# Board_Schematic.net
KiCad netlist of a schematic drawn in Altium Designer
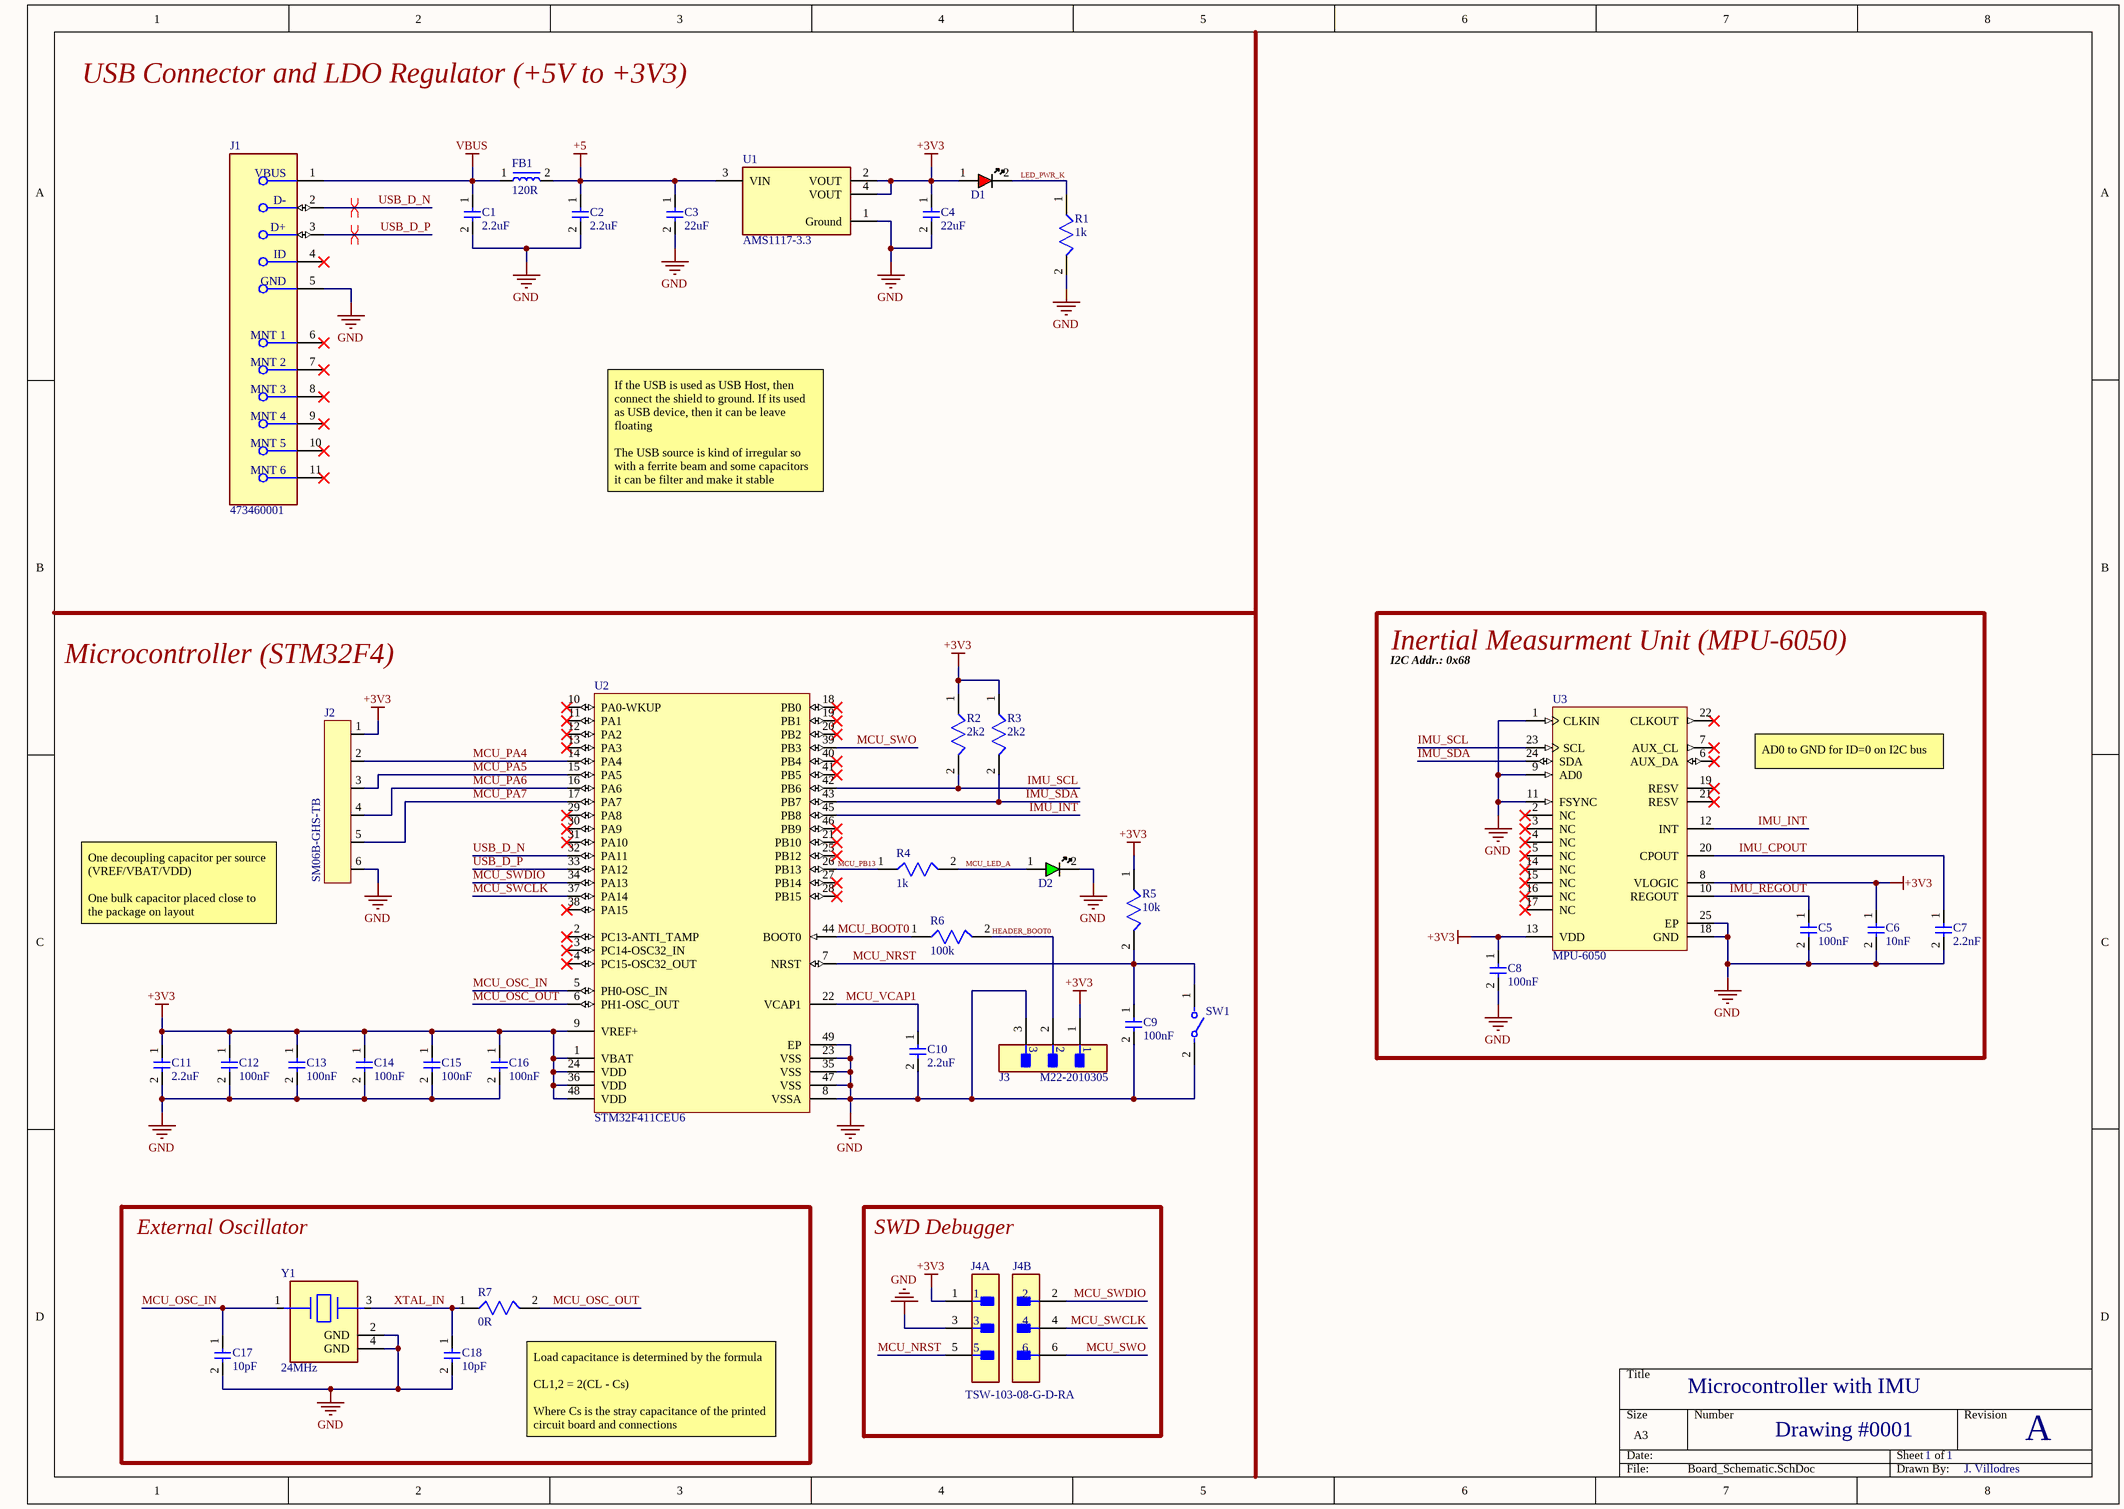
[diagram p0: Board_Schematic.SchDoc]

(export (version "E")
  (design (tool "Eeschema 10.0.6"))
  (components
    (comp (ref "C1")
      (value "2.2uF")
      (footprint "CAPC1608X90N")
      (description "Capacitor SMD 0603 16V")
      (libsource (lib "Schematic-Lib-JVillodres") (part "CAP_0603_16V"))
    )
    (comp (ref "C2")
      (value "2.2uF")
      (footprint "CAPC1608X90N")
      (description "Capacitor SMD 0603 16V")
      (libsource (lib "Schematic-Lib-JVillodres") (part "CAP_0603_16V"))
    )
    (comp (ref "C3")
      (value "22uF")
      (footprint "CAPC2012X95L")
      (description "Capacitor SMD 0805 16V")
      (libsource (lib "Schematic-Lib-JVillodres") (part "CAP_0805_16V"))
    )
    (comp (ref "C4")
      (value "22uF")
      (footprint "CAPC2012X95L")
      (description "Capacitor SMD 0805 16V")
      (libsource (lib "Schematic-Lib-JVillodres") (part "CAP_0805_16V"))
    )
    (comp (ref "C5")
      (value "100nF")
      (footprint "CAPC1005X55N")
      (description "Capacitor SMD 0402 16V")
      (libsource (lib "Schematic-Lib-JVillodres") (part "CAP_0402_16V"))
    )
    (comp (ref "C6")
      (value "10nF")
      (footprint "CAPC1005X55N")
      (description "Capacitor SMD 0402 16V")
      (libsource (lib "Schematic-Lib-JVillodres") (part "CAP_0402_16V"))
    )
    (comp (ref "C7")
      (value "2.2nF")
      (footprint "CAPC1005X55N")
      (description "Capacitor SMD 0402 16V")
      (libsource (lib "Schematic-Lib-JVillodres") (part "CAP_0402_16V"))
    )
    (comp (ref "C8")
      (value "100nF")
      (footprint "CAPC1005X55N")
      (description "Capacitor SMD 0402 16V")
      (libsource (lib "Schematic-Lib-JVillodres") (part "CAP_0402_16V"))
    )
    (comp (ref "C9")
      (value "100nF")
      (footprint "CAPC1005X55N")
      (description "Capacitor SMD 0402 16V")
      (libsource (lib "Schematic-Lib-JVillodres") (part "CAP_0402_16V"))
    )
    (comp (ref "C10")
      (value "2.2uF")
      (footprint "CAPC1608X90N")
      (description "Capacitor SMD 0603 16V")
      (libsource (lib "Schematic-Lib-JVillodres") (part "CAP_0603_16V"))
    )
    (comp (ref "C11")
      (value "2.2uF")
      (footprint "CAPC1608X90N")
      (description "Capacitor SMD 0603 16V")
      (libsource (lib "Schematic-Lib-JVillodres") (part "CAP_0603_16V"))
    )
    (comp (ref "C12")
      (value "100nF")
      (footprint "CAPC1005X55N")
      (description "Capacitor SMD 0402 16V")
      (libsource (lib "Schematic-Lib-JVillodres") (part "CAP_0402_16V"))
    )
    (comp (ref "C13")
      (value "100nF")
      (footprint "CAPC1005X55N")
      (description "Capacitor SMD 0402 16V")
      (libsource (lib "Schematic-Lib-JVillodres") (part "CAP_0402_16V"))
    )
    (comp (ref "C14")
      (value "100nF")
      (footprint "CAPC1005X55N")
      (description "Capacitor SMD 0402 16V")
      (libsource (lib "Schematic-Lib-JVillodres") (part "CAP_0402_16V"))
    )
    (comp (ref "C15")
      (value "100nF")
      (footprint "CAPC1005X55N")
      (description "Capacitor SMD 0402 16V")
      (libsource (lib "Schematic-Lib-JVillodres") (part "CAP_0402_16V"))
    )
    (comp (ref "C16")
      (value "100nF")
      (footprint "CAPC1005X55N")
      (description "Capacitor SMD 0402 16V")
      (libsource (lib "Schematic-Lib-JVillodres") (part "CAP_0402_16V"))
    )
    (comp (ref "C17")
      (value "10pF")
      (footprint "CAPC1005X55N")
      (description "Capacitor SMD 0402 16V")
      (libsource (lib "Schematic-Lib-JVillodres") (part "CAP_0402_16V"))
    )
    (comp (ref "C18")
      (value "10pF")
      (footprint "CAPC1005X55N")
      (description "Capacitor SMD 0402 16V")
      (libsource (lib "Schematic-Lib-JVillodres") (part "CAP_0402_16V"))
    )
    (comp (ref "D1")
      (value "LED_0402_RED")
      (footprint "LEDC0402")
      (description "LED RED SMD 0402")
      (libsource (lib "Schematic-Lib-JVillodres") (part "LED_0402_RED"))
    )
    (comp (ref "D2")
      (value "LED_0402_GREEN")
      (footprint "LEDC0402")
      (description "LED GREEN SMD 0402")
      (libsource (lib "Schematic-Lib-JVillodres") (part "LED_0402_GREEN"))
    )
    (comp (ref "FB1")
      (value "120R")
      (footprint "FBC1608X95L")
      (description "Ferrite Bead SMD 0603")
      (libsource (lib "Schematic-Lib-JVillodres") (part "FB_0603"))
    )
    (comp (ref "J1")
      (value "473460001")
      (footprint "FP-473460001-MFG")
      (description "CONN RCPT USB2.0 MICRO B SMD R/A")
      (fields
        (field (name "OCTOPART") "https://octopart.com/47346-0001-molex-7164928")
        (field (name "MANUFACTURER") "Molex")
      )
      (libsource (lib "Altium Content Vault") (part "53ae1f1d9b557310b43ca686e5bb76a"))
    )
    (comp (ref "J2")
      (value "SM06B-GHS-TB")
      (footprint "SM06B-GHS-TB")
      (description "Header Connector 6-Pin")
      (libsource (lib "Schematic-Lib-JVillodres") (part "SM06B-GHS-TB"))
    )
    (comp (ref "J3")
      (value "M22-2010305")
      (footprint "FP-M22-2010305-MFG")
      (description "CONN HEADER VERT 3POS 2MM")
      (libsource (lib "Altium Content Vault") (part "d6a96a410146d2d686cfe982f2af7ec"))
    )
    (comp (ref "J4")
      (value "TSW-103-08-G-D-RA")
      (footprint "FP-TSW-103-08-G-D-RA-MFG")
      (description "CONN HEADER R/A 6POS 2.54MM")
      (libsource (lib "") (part "2654a11fb13586ecb194516b1c997bc_1"))
    )
    (comp (ref "R1")
      (value "1k")
      (footprint "RESC1005X37L")
      (description "Resistor SMD 0402")
      (libsource (lib "Schematic-Lib-JVillodres") (part "RES_0402"))
    )
    (comp (ref "R2")
      (value "2k2")
      (footprint "RESC1005X37L")
      (description "Resistor SMD 0402")
      (libsource (lib "Schematic-Lib-JVillodres") (part "RES_0402"))
    )
    (comp (ref "R3")
      (value "2k2")
      (footprint "RESC1005X37L")
      (description "Resistor SMD 0402")
      (libsource (lib "Schematic-Lib-JVillodres") (part "RES_0402"))
    )
    (comp (ref "R4")
      (value "1k")
      (footprint "RESC1005X37L")
      (description "Resistor SMD 0402")
      (libsource (lib "Schematic-Lib-JVillodres") (part "RES_0402"))
    )
    (comp (ref "R5")
      (value "10k")
      (footprint "RESC1005X37N")
      (description "Resistor SMD 0402")
      (libsource (lib "Schematic-Lib-JVillodres") (part "RES_0402"))
    )
    (comp (ref "R6")
      (value "100k")
      (footprint "RESC1005X37N")
      (description "Resistor SMD 0402")
      (libsource (lib "Schematic-Lib-JVillodres") (part "RES_0402"))
    )
    (comp (ref "R7")
      (value "0R")
      (footprint "RESC1005X37N")
      (description "Resistor SMD 0402")
      (libsource (lib "Schematic-Lib-JVillodres") (part "RES_0402"))
    )
    (comp (ref "SW1")
      (value "147873-2")
      (footprint "FP-147873-2-MFG")
      (description "SWITCH TACTILE SPST-NO 0.05A 24V")
      (libsource (lib "Altium Content Vault") (part "dafb00e05129bbbb566f246498240cb"))
    )
    (comp (ref "U1")
      (value "AMS1117-3.3")
      (footprint "FP-AMS1117-IPC_C")
      (description "LDO Voltage Regulators 1A, 3.3V")
      (fields
        (field (name "OCTOPART") "https://octopart.com/ams1117-3.3-advanced+monolithic+systems-25899300")
        (field (name "MANUFACTURER") "Advanced Monolithic Systems")
      )
      (libsource (lib "Altium Content Vault") (part "8bdbb5f8e77002000e30dd2845d0354"))
    )
    (comp (ref "U2")
      (value "STM32F411CEU6")
      (footprint "STM-UFQFPN48_L")
      (libsource (lib "Altium Content Vault") (part "MC-ARM-STM32F411-UFQFPN48"))
    )
    (comp (ref "U3")
      (value "MPU-6050")
      (footprint "IS-QFN-24_V")
      (fields (field (name "MANUFACTURER") "InvenSense"))
      (libsource (lib "Altium Content Vault") (part "IS-MPU-6050-QFN-24"))
    )
    (comp (ref "Y1")
      (value "24MHz")
      (footprint "FP-TSX-3225-MFG")
      (description "CRYSTAL 24.0000MHZ 9PF SMD")
      (fields (field (name "TOLERANCE") "10ppm"))
      (libsource (lib "Altium Content Vault") (part "862d5228ea4a4c8f16e8fb874e464c7"))
    )
  )
  (nets
    (net (code "1") (name "+3V3") (class "Default")
      (node (ref "C11") (pin "1") (pintype "passive"))
      (node (ref "C12") (pin "1") (pintype "passive"))
      (node (ref "C13") (pin "1") (pintype "passive"))
      (node (ref "C14") (pin "1") (pintype "passive"))
      (node (ref "C15") (pin "1") (pintype "passive"))
      (node (ref "C16") (pin "1") (pintype "passive"))
      (node (ref "C4") (pin "1") (pintype "passive"))
      (node (ref "C6") (pin "1") (pintype "passive"))
      (node (ref "C8") (pin "1") (pintype "passive"))
      (node (ref "D1") (pin "1") (pinfunction "A_1") (pintype "passive"))
      (node (ref "J2") (pin "1") (pintype "passive"))
      (node (ref "J3") (pin "1") (pinfunction "1_1") (pintype "passive"))
      (node (ref "J4") (pin "1") (pinfunction "1_1") (pintype "passive"))
      (node (ref "R2") (pin "1") (pintype "passive"))
      (node (ref "R3") (pin "1") (pintype "passive"))
      (node (ref "R5") (pin "1") (pintype "passive"))
      (node (ref "U1") (pin "2") (pinfunction "VOUT_2") (pintype "passive"))
      (node (ref "U1") (pin "4") (pinfunction "VOUT_4") (pintype "passive"))
      (node (ref "U2") (pin "1") (pinfunction "VBAT_1") (pintype "power_in"))
      (node (ref "U2") (pin "24") (pinfunction "VDD_24") (pintype "power_in"))
      (node (ref "U2") (pin "36") (pinfunction "VDD_36") (pintype "power_in"))
      (node (ref "U2") (pin "48") (pinfunction "VDD_48") (pintype "power_in"))
      (node (ref "U2") (pin "9") (pinfunction "VREF+_9") (pintype "power_in"))
      (node (ref "U3") (pin "13") (pinfunction "VDD_13") (pintype "power_in"))
      (node (ref "U3") (pin "8") (pinfunction "VLOGIC_8") (pintype "power_in"))
    )
    (net (code "2") (name "+5") (class "Default")
      (node (ref "C2") (pin "1") (pintype "passive"))
      (node (ref "C3") (pin "1") (pintype "passive"))
      (node (ref "FB1") (pin "2") (pinfunction "2_2") (pintype "passive"))
      (node (ref "U1") (pin "3") (pinfunction "VIN_3") (pintype "power_in"))
    )
    (net (code "3") (name "/HEADER_BOOT0") (class "Default")
      (node (ref "J3") (pin "2") (pinfunction "2_2") (pintype "passive"))
      (node (ref "R6") (pin "2") (pintype "passive"))
    )
    (net (code "4") (name "/IMU_CPOUT") (class "Default")
      (node (ref "C7") (pin "1") (pintype "passive"))
      (node (ref "U3") (pin "20") (pinfunction "CPOUT_20") (pintype "passive"))
    )
    (net (code "5") (name "/IMU_INT") (class "Default")
      (node (ref "U2") (pin "45") (pinfunction "PB8_45") (pintype "bidirectional"))
      (node (ref "U3") (pin "12") (pinfunction "INT_12") (pintype "open_collector"))
    )
    (net (code "6") (name "/IMU_REGOUT") (class "Default")
      (node (ref "C5") (pin "1") (pintype "passive"))
      (node (ref "U3") (pin "10") (pinfunction "REGOUT_10") (pintype "passive"))
    )
    (net (code "7") (name "/IMU_SCL") (class "Default")
      (node (ref "R2") (pin "2") (pintype "passive"))
      (node (ref "U2") (pin "42") (pinfunction "PB6_42") (pintype "bidirectional"))
      (node (ref "U3") (pin "23") (pinfunction "SCL_23") (pintype "input"))
    )
    (net (code "8") (name "/IMU_SDA") (class "Default")
      (node (ref "R3") (pin "2") (pintype "passive"))
      (node (ref "U2") (pin "43") (pinfunction "PB7_43") (pintype "bidirectional"))
      (node (ref "U3") (pin "24") (pinfunction "SDA_24") (pintype "bidirectional"))
    )
    (net (code "9") (name "/LED_PWR_K") (class "Default")
      (node (ref "D1") (pin "2") (pinfunction "K_2") (pintype "passive"))
      (node (ref "R1") (pin "1") (pintype "passive"))
    )
    (net (code "10") (name "/MCU_BOOT0") (class "Default")
      (node (ref "R6") (pin "1") (pintype "passive"))
      (node (ref "U2") (pin "44") (pinfunction "BOOT0_44") (pintype "input"))
    )
    (net (code "11") (name "/MCU_LED_A") (class "Default")
      (node (ref "D2") (pin "1") (pinfunction "A_1") (pintype "passive"))
      (node (ref "R4") (pin "2") (pintype "passive"))
    )
    (net (code "12") (name "/MCU_NRST") (class "Default")
      (node (ref "C9") (pin "1") (pintype "passive"))
      (node (ref "J4") (pin "5") (pinfunction "5_5") (pintype "passive"))
      (node (ref "R5") (pin "2") (pintype "passive"))
      (node (ref "SW1") (pin "1") (pinfunction "1_1") (pintype "passive"))
      (node (ref "U2") (pin "7") (pinfunction "NRST_7") (pintype "bidirectional"))
    )
    (net (code "13") (name "/MCU_OSC_IN") (class "Default")
      (node (ref "C17") (pin "1") (pintype "passive"))
      (node (ref "U2") (pin "5") (pinfunction "PH0-OSC_IN_5") (pintype "bidirectional"))
      (node (ref "Y1") (pin "1") (pinfunction "1_1") (pintype "passive"))
    )
    (net (code "14") (name "/MCU_OSC_OUT") (class "Default")
      (node (ref "R7") (pin "2") (pintype "passive"))
      (node (ref "U2") (pin "6") (pinfunction "PH1-OSC_OUT_6") (pintype "bidirectional"))
    )
    (net (code "15") (name "/MCU_PA4") (class "Default")
      (node (ref "J2") (pin "2") (pintype "passive"))
      (node (ref "U2") (pin "14") (pinfunction "PA4_14") (pintype "bidirectional"))
    )
    (net (code "16") (name "/MCU_PA5") (class "Default")
      (node (ref "J2") (pin "3") (pintype "passive"))
      (node (ref "U2") (pin "15") (pinfunction "PA5_15") (pintype "bidirectional"))
    )
    (net (code "17") (name "/MCU_PA6") (class "Default")
      (node (ref "J2") (pin "4") (pintype "passive"))
      (node (ref "U2") (pin "16") (pinfunction "PA6_16") (pintype "bidirectional"))
    )
    (net (code "18") (name "/MCU_PA7") (class "Default")
      (node (ref "J2") (pin "5") (pintype "passive"))
      (node (ref "U2") (pin "17") (pinfunction "PA7_17") (pintype "bidirectional"))
    )
    (net (code "19") (name "/MCU_PB13") (class "Default")
      (node (ref "R4") (pin "1") (pintype "passive"))
      (node (ref "U2") (pin "26") (pinfunction "PB13_26") (pintype "bidirectional"))
    )
    (net (code "20") (name "/MCU_SWCLK") (class "Default")
      (node (ref "J4") (pin "4") (pinfunction "4_4") (pintype "passive"))
      (node (ref "U2") (pin "37") (pinfunction "PA14_37") (pintype "bidirectional"))
    )
    (net (code "21") (name "/MCU_SWDIO") (class "Default")
      (node (ref "J4") (pin "2") (pinfunction "2_2") (pintype "passive"))
      (node (ref "U2") (pin "34") (pinfunction "PA13_34") (pintype "bidirectional"))
    )
    (net (code "22") (name "/MCU_SWO") (class "Default")
      (node (ref "J4") (pin "6") (pinfunction "6_6") (pintype "passive"))
      (node (ref "U2") (pin "39") (pinfunction "PB3_39") (pintype "bidirectional"))
    )
    (net (code "23") (name "/MCU_VCAP1") (class "Default")
      (node (ref "C10") (pin "1") (pintype "passive"))
      (node (ref "U2") (pin "22") (pinfunction "VCAP1_22") (pintype "passive"))
    )
    (net (code "24") (name "/USB_D_N") (class "Default")
      (node (ref "J1") (pin "2") (pinfunction "D-_2") (pintype "bidirectional"))
      (node (ref "U2") (pin "32") (pinfunction "PA11_32") (pintype "bidirectional"))
    )
    (net (code "25") (name "/USB_D_P") (class "Default")
      (node (ref "J1") (pin "3") (pinfunction "D+_3") (pintype "bidirectional"))
      (node (ref "U2") (pin "33") (pinfunction "PA12_33") (pintype "bidirectional"))
    )
    (net (code "26") (name "/XTAL_IN") (class "Default")
      (node (ref "C18") (pin "1") (pintype "passive"))
      (node (ref "R7") (pin "1") (pintype "passive"))
      (node (ref "Y1") (pin "3") (pinfunction "3_3") (pintype "passive"))
    )
    (net (code "27") (name "GND") (class "Default")
      (node (ref "C1") (pin "2") (pintype "passive"))
      (node (ref "C10") (pin "2") (pintype "passive"))
      (node (ref "C11") (pin "2") (pintype "passive"))
      (node (ref "C12") (pin "2") (pintype "passive"))
      (node (ref "C13") (pin "2") (pintype "passive"))
      (node (ref "C14") (pin "2") (pintype "passive"))
      (node (ref "C15") (pin "2") (pintype "passive"))
      (node (ref "C16") (pin "2") (pintype "passive"))
      (node (ref "C17") (pin "2") (pintype "passive"))
      (node (ref "C18") (pin "2") (pintype "passive"))
      (node (ref "C2") (pin "2") (pintype "passive"))
      (node (ref "C3") (pin "2") (pintype "passive"))
      (node (ref "C4") (pin "2") (pintype "passive"))
      (node (ref "C5") (pin "2") (pintype "passive"))
      (node (ref "C6") (pin "2") (pintype "passive"))
      (node (ref "C7") (pin "2") (pintype "passive"))
      (node (ref "C8") (pin "2") (pintype "passive"))
      (node (ref "C9") (pin "2") (pintype "passive"))
      (node (ref "D2") (pin "2") (pinfunction "K_2") (pintype "passive"))
      (node (ref "J1") (pin "5") (pinfunction "GND_5") (pintype "power_in"))
      (node (ref "J2") (pin "6") (pintype "passive"))
      (node (ref "J3") (pin "3") (pinfunction "3_3") (pintype "passive"))
      (node (ref "J4") (pin "3") (pinfunction "3_3") (pintype "passive"))
      (node (ref "R1") (pin "2") (pintype "passive"))
      (node (ref "SW1") (pin "2") (pinfunction "2_2") (pintype "passive"))
      (node (ref "U1") (pin "1") (pinfunction "Ground_1") (pintype "power_in"))
      (node (ref "U2") (pin "23") (pinfunction "VSS_23") (pintype "power_in"))
      (node (ref "U2") (pin "35") (pinfunction "VSS_35") (pintype "power_in"))
      (node (ref "U2") (pin "47") (pinfunction "VSS_47") (pintype "power_in"))
      (node (ref "U2") (pin "49") (pinfunction "EP_49") (pintype "power_in"))
      (node (ref "U2") (pin "8") (pinfunction "VSSA_8") (pintype "power_in"))
      (node (ref "U3") (pin "1") (pinfunction "CLKIN_1") (pintype "input"))
      (node (ref "U3") (pin "11") (pinfunction "FSYNC_11") (pintype "input"))
      (node (ref "U3") (pin "18") (pinfunction "GND_18") (pintype "power_in"))
      (node (ref "U3") (pin "25") (pinfunction "EP_25") (pintype "power_in"))
      (node (ref "U3") (pin "9") (pinfunction "AD0_9") (pintype "input"))
      (node (ref "Y1") (pin "2") (pinfunction "GND_2") (pintype "power_in"))
      (node (ref "Y1") (pin "4") (pinfunction "GND_4") (pintype "power_in"))
    )
    (net (code "28") (name "VBUS") (class "Default")
      (node (ref "C1") (pin "1") (pintype "passive"))
      (node (ref "FB1") (pin "1") (pinfunction "1_1") (pintype "passive"))
      (node (ref "J1") (pin "1") (pinfunction "VBUS_1") (pintype "power_in"))
    )
    (net (code "29") (name "unconnected-(J1-ID-Pad4)") (class "Default")
      (node (ref "J1") (pin "4") (pinfunction "ID_4") (pintype "passive+no_connect"))
    )
    (net (code "30") (name "unconnected-(J1-MNT_1-Pad6)") (class "Default")
      (node (ref "J1") (pin "6") (pinfunction "MNT_1_6") (pintype "passive+no_connect"))
    )
    (net (code "31") (name "unconnected-(J1-MNT_2-Pad7)") (class "Default")
      (node (ref "J1") (pin "7") (pinfunction "MNT_2_7") (pintype "passive+no_connect"))
    )
    (net (code "32") (name "unconnected-(J1-MNT_3-Pad8)") (class "Default")
      (node (ref "J1") (pin "8") (pinfunction "MNT_3_8") (pintype "passive+no_connect"))
    )
    (net (code "33") (name "unconnected-(J1-MNT_4-Pad9)") (class "Default")
      (node (ref "J1") (pin "9") (pinfunction "MNT_4_9") (pintype "passive+no_connect"))
    )
    (net (code "34") (name "unconnected-(J1-MNT_5-Pad10)") (class "Default")
      (node (ref "J1") (pin "10") (pinfunction "MNT_5_10") (pintype "passive+no_connect"))
    )
    (net (code "35") (name "unconnected-(J1-MNT_6-Pad11)") (class "Default")
      (node (ref "J1") (pin "11") (pinfunction "MNT_6_11") (pintype "passive+no_connect"))
    )
    (net (code "36") (name "unconnected-(U2-PA0-WKUP-Pad10)") (class "Default")
      (node (ref "U2") (pin "10") (pinfunction "PA0-WKUP_10") (pintype "bidirectional+no_connect"))
    )
    (net (code "37") (name "unconnected-(U2-PA1-Pad11)") (class "Default")
      (node (ref "U2") (pin "11") (pinfunction "PA1_11") (pintype "bidirectional+no_connect"))
    )
    (net (code "38") (name "unconnected-(U2-PA2-Pad12)") (class "Default")
      (node (ref "U2") (pin "12") (pinfunction "PA2_12") (pintype "bidirectional+no_connect"))
    )
    (net (code "39") (name "unconnected-(U2-PA3-Pad13)") (class "Default")
      (node (ref "U2") (pin "13") (pinfunction "PA3_13") (pintype "bidirectional+no_connect"))
    )
    (net (code "40") (name "unconnected-(U2-PA8-Pad29)") (class "Default")
      (node (ref "U2") (pin "29") (pinfunction "PA8_29") (pintype "bidirectional+no_connect"))
    )
    (net (code "41") (name "unconnected-(U2-PA9-Pad30)") (class "Default")
      (node (ref "U2") (pin "30") (pinfunction "PA9_30") (pintype "bidirectional+no_connect"))
    )
    (net (code "42") (name "unconnected-(U2-PA10-Pad31)") (class "Default")
      (node (ref "U2") (pin "31") (pinfunction "PA10_31") (pintype "bidirectional+no_connect"))
    )
    (net (code "43") (name "unconnected-(U2-PA15-Pad38)") (class "Default")
      (node (ref "U2") (pin "38") (pinfunction "PA15_38") (pintype "bidirectional+no_connect"))
    )
    (net (code "44") (name "unconnected-(U2-PB0-Pad18)") (class "Default")
      (node (ref "U2") (pin "18") (pinfunction "PB0_18") (pintype "bidirectional+no_connect"))
    )
    (net (code "45") (name "unconnected-(U2-PB1-Pad19)") (class "Default")
      (node (ref "U2") (pin "19") (pinfunction "PB1_19") (pintype "bidirectional+no_connect"))
    )
    (net (code "46") (name "unconnected-(U2-PB2-Pad20)") (class "Default")
      (node (ref "U2") (pin "20") (pinfunction "PB2_20") (pintype "bidirectional+no_connect"))
    )
    (net (code "47") (name "unconnected-(U2-PB4-Pad40)") (class "Default")
      (node (ref "U2") (pin "40") (pinfunction "PB4_40") (pintype "bidirectional+no_connect"))
    )
    (net (code "48") (name "unconnected-(U2-PB5-Pad41)") (class "Default")
      (node (ref "U2") (pin "41") (pinfunction "PB5_41") (pintype "bidirectional+no_connect"))
    )
    (net (code "49") (name "unconnected-(U2-PB9-Pad46)") (class "Default")
      (node (ref "U2") (pin "46") (pinfunction "PB9_46") (pintype "bidirectional+no_connect"))
    )
    (net (code "50") (name "unconnected-(U2-PB10-Pad21)") (class "Default")
      (node (ref "U2") (pin "21") (pinfunction "PB10_21") (pintype "bidirectional+no_connect"))
    )
    (net (code "51") (name "unconnected-(U2-PB12-Pad25)") (class "Default")
      (node (ref "U2") (pin "25") (pinfunction "PB12_25") (pintype "bidirectional+no_connect"))
    )
    (net (code "52") (name "unconnected-(U2-PB14-Pad27)") (class "Default")
      (node (ref "U2") (pin "27") (pinfunction "PB14_27") (pintype "bidirectional+no_connect"))
    )
    (net (code "53") (name "unconnected-(U2-PB15-Pad28)") (class "Default")
      (node (ref "U2") (pin "28") (pinfunction "PB15_28") (pintype "bidirectional+no_connect"))
    )
    (net (code "54") (name "unconnected-(U2-PC13-ANTI_TAMP-Pad2)") (class "Default")
      (node (ref "U2") (pin "2") (pinfunction "PC13-ANTI_TAMP_2") (pintype "bidirectional+no_connect"))
    )
    (net (code "55") (name "unconnected-(U2-PC14-OSC32_IN-Pad3)") (class "Default")
      (node (ref "U2") (pin "3") (pinfunction "PC14-OSC32_IN_3") (pintype "bidirectional+no_connect"))
    )
    (net (code "56") (name "unconnected-(U2-PC15-OSC32_OUT-Pad4)") (class "Default")
      (node (ref "U2") (pin "4") (pinfunction "PC15-OSC32_OUT_4") (pintype "bidirectional+no_connect"))
    )
    (net (code "57") (name "unconnected-(U3-AUX_CL-Pad7)") (class "Default")
      (node (ref "U3") (pin "7") (pinfunction "AUX_CL_7") (pintype "output+no_connect"))
    )
    (net (code "58") (name "unconnected-(U3-AUX_DA-Pad6)") (class "Default")
      (node (ref "U3") (pin "6") (pinfunction "AUX_DA_6") (pintype "bidirectional+no_connect"))
    )
    (net (code "59") (name "unconnected-(U3-CLKOUT-Pad22)") (class "Default")
      (node (ref "U3") (pin "22") (pinfunction "CLKOUT_22") (pintype "output+no_connect"))
    )
    (net (code "60") (name "unconnected-(U3-NC-Pad2)") (class "Default")
      (node (ref "U3") (pin "2") (pinfunction "NC_2") (pintype "passive+no_connect"))
    )
    (net (code "61") (name "unconnected-(U3-NC-Pad3)") (class "Default")
      (node (ref "U3") (pin "3") (pinfunction "NC_3") (pintype "passive+no_connect"))
    )
    (net (code "62") (name "unconnected-(U3-NC-Pad4)") (class "Default")
      (node (ref "U3") (pin "4") (pinfunction "NC_4") (pintype "passive+no_connect"))
    )
    (net (code "63") (name "unconnected-(U3-NC-Pad5)") (class "Default")
      (node (ref "U3") (pin "5") (pinfunction "NC_5") (pintype "passive+no_connect"))
    )
    (net (code "64") (name "unconnected-(U3-NC-Pad14)") (class "Default")
      (node (ref "U3") (pin "14") (pinfunction "NC_14") (pintype "passive+no_connect"))
    )
    (net (code "65") (name "unconnected-(U3-NC-Pad15)") (class "Default")
      (node (ref "U3") (pin "15") (pinfunction "NC_15") (pintype "passive+no_connect"))
    )
    (net (code "66") (name "unconnected-(U3-NC-Pad16)") (class "Default")
      (node (ref "U3") (pin "16") (pinfunction "NC_16") (pintype "passive+no_connect"))
    )
    (net (code "67") (name "unconnected-(U3-NC-Pad17)") (class "Default")
      (node (ref "U3") (pin "17") (pinfunction "NC_17") (pintype "passive+no_connect"))
    )
    (net (code "68") (name "unconnected-(U3-RESV-Pad19)") (class "Default")
      (node (ref "U3") (pin "19") (pinfunction "RESV_19") (pintype "passive+no_connect"))
    )
    (net (code "69") (name "unconnected-(U3-RESV-Pad21)") (class "Default")
      (node (ref "U3") (pin "21") (pinfunction "RESV_21") (pintype "passive+no_connect"))
    )
  )
)
